# BSPD.net
KiCad netlist of a schematic drawn in Altium Designer
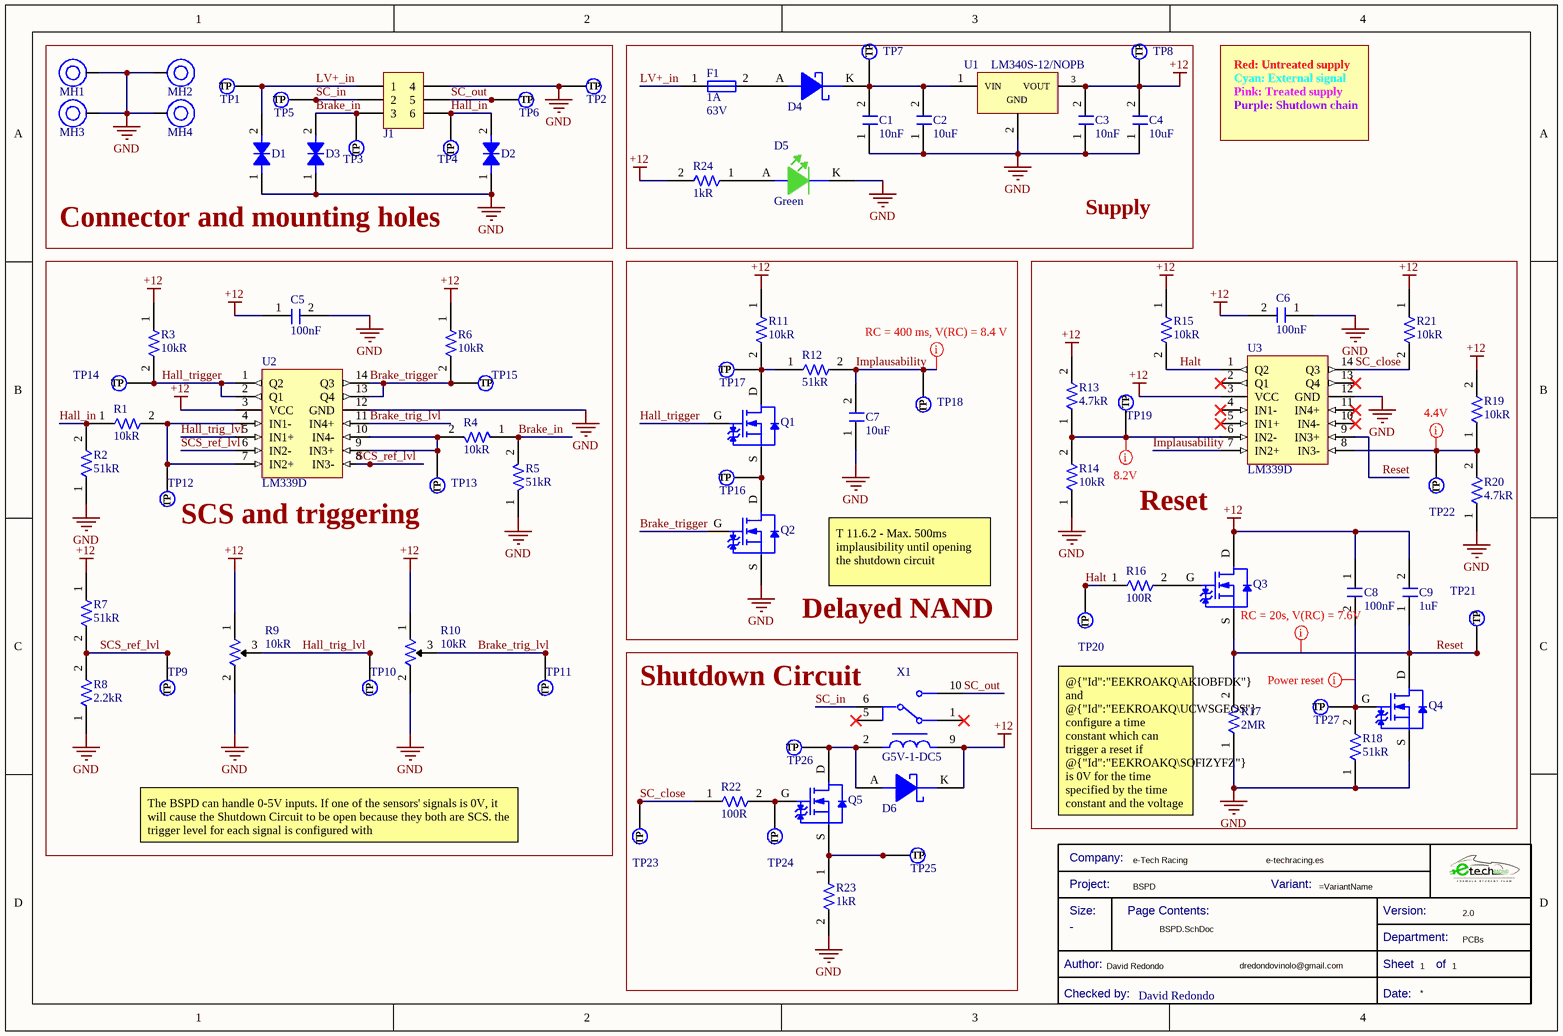
[diagram p0: BSPD.SchDoc]

(export (version "E")
  (design (tool "Eeschema 10.0.6"))
  (components
    (comp (ref "*")
      (value "Title Block_template")
      (description "Standard Title Block")
      (fields
        (field (name "SIZE") "-")
        (field (name ".CREATOR") "GP")
        (field (name ".PCBCHECK") "GP")
        (field (name ".SCHCHECK") "GP")
      )
      (libsource (lib "e-Tech_Racing") (part "Title Block_template"))
    )
    (comp (ref "C1")
      (value "885012008055")
      (footprint "C1206FNPC-RW")
      (description "Cap Cer 10000PF 50V C0G/NP0 1206")
      (fields
        (field (name "MANUFACTURER") "Wurth Electronics")
        (field (name "TOLERANCE") "5%")
        (field (name "CAPACITANCE") "10nF")
        (field (name ".CREATOR") "DO")
      )
      (libsource (lib "Passives") (part "C10n-50V-1206FNPC-C0G/NP0"))
    )
    (comp (ref "C2")
      (value "GRJ32ER71H106KE11L")
      (footprint "C10u-50V-1210FNPMLCC-X7R")
      (description "Multilayer Ceramic Capacitors MLCC - SMD/SMT 1210 10uF 50volts X7R +/-10% Soft Term")
      (fields
        (field (name "MANUFACTURER") "Murata")
        (field (name "TOLERANCE") "10%")
        (field (name "CAPACITANCE") "10uF")
        (field (name ".CREATOR") "DR")
      )
      (libsource (lib "Passives") (part "C10u-50V-1210FNPMLCC-X7R"))
    )
    (comp (ref "C3")
      (value "885012008055")
      (footprint "C1206FNPC-RW")
      (description "Cap Cer 10000PF 50V C0G/NP0 1206")
      (fields
        (field (name "MANUFACTURER") "Wurth Electronics")
        (field (name "TOLERANCE") "5%")
        (field (name "CAPACITANCE") "10nF")
        (field (name ".CREATOR") "DO")
      )
      (libsource (lib "Passives") (part "C10n-50V-1206FNPC-C0G/NP0"))
    )
    (comp (ref "C4")
      (value "GRJ32ER71H106KE11L")
      (footprint "C10u-50V-1210FNPMLCC-X7R")
      (description "Multilayer Ceramic Capacitors MLCC - SMD/SMT 1210 10uF 50volts X7R +/-10% Soft Term")
      (fields
        (field (name "MANUFACTURER") "Murata")
        (field (name "TOLERANCE") "10%")
        (field (name "CAPACITANCE") "10uF")
        (field (name ".CREATOR") "DR")
      )
      (libsource (lib "Passives") (part "C10u-50V-1210FNPMLCC-X7R"))
    )
    (comp (ref "C5")
      (value "885012208058")
      (footprint "C1206FNPC-RW")
      (description "Cap Cer 0.1UF 25V X7R 1206")
      (fields
        (field (name "MANUFACTURER") "Wurth Electronics")
        (field (name "TOLERANCE") "10%")
        (field (name "CAPACITANCE") "100nF")
        (field (name ".CREATOR") "DO")
      )
      (libsource (lib "Passives") (part "C100n-25V-1206FNPC-X7R"))
    )
    (comp (ref "C6")
      (value "885012208058")
      (footprint "C1206FNPC-RW")
      (description "Cap Cer 0.1UF 25V X7R 1206")
      (fields
        (field (name "MANUFACTURER") "Wurth Electronics")
        (field (name "TOLERANCE") "10%")
        (field (name "CAPACITANCE") "100nF")
        (field (name ".CREATOR") "DO")
      )
      (libsource (lib "Passives") (part "C100n-25V-1206FNPC-X7R"))
    )
    (comp (ref "C7")
      (value "885012208018")
      (footprint "C1206FNPC-RW")
      (description "Cap, 10ΜF, 10V, 10%, X7R, 1206")
      (fields
        (field (name "TOLERANCE") "10%")
        (field (name "CAPACITANCE") "10uF")
        (field (name ".CREATOR") "GP")
      )
      (libsource (lib "Passives") (part "C10u-10V-1206FNPC-X7R"))
    )
    (comp (ref "C8")
      (value "885012208058")
      (footprint "C1206FNPC-RW")
      (description "Cap Cer 0.1UF 25V X7R 1206")
      (fields
        (field (name "MANUFACTURER") "Wurth Electronics")
        (field (name "TOLERANCE") "10%")
        (field (name "CAPACITANCE") "100nF")
        (field (name ".CREATOR") "DO")
      )
      (libsource (lib "Passives") (part "C100n-25V-1206FNPC-X7R"))
    )
    (comp (ref "C9")
      (value "885012208036")
      (footprint "C1206FNPC-RW")
      (description "Cap Cer 1UF 16V X7R 1206")
      (fields
        (field (name "MANUFACTURER") "Wurth Electronics")
        (field (name "TOLERANCE") "10%")
        (field (name "CAPACITANCE") "1uF")
        (field (name ".CREATOR") "GP")
      )
      (libsource (lib "Passives") (part "C1u-16V-1206FNPC-X7R"))
    )
    (comp (ref "D1")
      (value "824551301")
      (footprint "DTVS-DO-214AB")
      (description "TVS diode [Würth Elektronik] 824551301 TVS diode")
      (fields (field (name "MANUFACTURER") "Wurth Electronics") (field (name ".CREATOR") "DO"))
      (libsource (lib "Filter components") (part "DTVS-40V-DO-214AB"))
    )
    (comp (ref "D2")
      (value "824501600")
      (footprint "DTVS-DO-214AC")
      (description "TVS diode [Würth Elektronik] 824501600 TVS diode")
      (fields (field (name "MANUFACTURER") "Wurth Electronics") (field (name ".CREATOR") "DO"))
      (libsource (lib "Filter components") (part "DTVS-6V-DO-214AC"))
    )
    (comp (ref "D3")
      (value "824501600")
      (footprint "DTVS-DO-214AC")
      (description "TVS diode [Würth Elektronik] 824501600 TVS diode")
      (fields (field (name "MANUFACTURER") "Wurth Electronics") (field (name ".CREATOR") "DO"))
      (libsource (lib "Filter components") (part "DTVS-6V-DO-214AC"))
    )
    (comp (ref "D4")
      (value "MBR0530")
      (footprint "DSC-SOD123")
      (description "VR=30V IF=500mA 30pF P=410mW")
      (fields (field (name ".CREATOR") "GP"))
      (libsource (lib "Filter components") (part "DSC-0.5/30-SOD123"))
    )
    (comp (ref "D5")
      (value "150080VS75000")
      (footprint "LED_0805_WE")
      (description "Led, Green, 570 Nm, 2 V, 30 Ma, 40 Mcd Rohs Compliant: Yes")
      (fields (field (name "COLOR") "Green") (field (name ".CREATOR") "DR"))
      (libsource (lib "Semiconductor") (part "LEDVS-0805-40"))
    )
    (comp (ref "D6")
      (value "MBR0530")
      (footprint "DSC-SOD123")
      (description "VR=30V IF=500mA 30pF P=410mW")
      (fields (field (name ".CREATOR") "GP"))
      (libsource (lib "Filter components") (part "DSC-0.5/30-SOD123"))
    )
    (comp (ref "F1")
      (value "0437001.WRA")
      (footprint "Fuse_1206")
      (description "Fuse Chip Fast Acting 1A 63V SMD Solder Pad 1206 Ceramic T/R Automotive")
      (fields
        (field (name "MANUFACTURER") "Littelfuse")
        (field (name "CURRENT RATING") "1A")
        (field (name "VOLTAGE RATING (DC)") "63V")
        (field (name ".CREATOR") "DO")
      )
      (libsource (lib "Filter components") (part "Fuse_1A_63V_1206"))
    )
    (comp (ref "J1")
      (value "J_NanoFit_2x3")
      (footprint "J_NanoFit_2x3")
      (libsource (lib "Electromechanical") (part "J_NanoFit_2x3"))
    )
    (comp (ref "MH1")
      (value "Mounting_Hole_M3")
      (footprint "Mounting_Hole_M3")
      (libsource (lib "Electromechanical") (part "Mounting_Hole_M3"))
    )
    (comp (ref "MH2")
      (value "Mounting_Hole_M3")
      (footprint "Mounting_Hole_M3")
      (libsource (lib "Electromechanical") (part "Mounting_Hole_M3"))
    )
    (comp (ref "MH3")
      (value "Mounting_Hole_M3")
      (footprint "Mounting_Hole_M3")
      (libsource (lib "Electromechanical") (part "Mounting_Hole_M3"))
    )
    (comp (ref "MH4")
      (value "Mounting_Hole_M3")
      (footprint "Mounting_Hole_M3")
      (libsource (lib "Electromechanical") (part "Mounting_Hole_M3"))
    )
    (comp (ref "Q1")
      (value "CPH3455-TL-H")
      (footprint "TRT-NCH-3/35-CPH")
      (description "CPH3455-TL-H N-channel MOSFET Transistor; 3 A; 35 V; 3-Pin CPH")
      (fields (field (name "MANUFACTURER") "ON Semiconductor") (field (name ".CREATOR") "GP"))
      (libsource (lib "Semiconductor") (part "TRT-NCH-3/35-CPH"))
    )
    (comp (ref "Q2")
      (value "CPH3455-TL-H")
      (footprint "TRT-NCH-3/35-CPH")
      (description "CPH3455-TL-H N-channel MOSFET Transistor; 3 A; 35 V; 3-Pin CPH")
      (fields (field (name "MANUFACTURER") "ON Semiconductor") (field (name ".CREATOR") "GP"))
      (libsource (lib "Semiconductor") (part "TRT-NCH-3/35-CPH"))
    )
    (comp (ref "Q3")
      (value "CPH3455-TL-H")
      (footprint "TRT-NCH-3/35-CPH")
      (description "CPH3455-TL-H N-channel MOSFET Transistor; 3 A; 35 V; 3-Pin CPH")
      (fields (field (name "MANUFACTURER") "ON Semiconductor") (field (name ".CREATOR") "GP"))
      (libsource (lib "Semiconductor") (part "TRT-NCH-3/35-CPH"))
    )
    (comp (ref "Q4")
      (value "CPH3455-TL-H")
      (footprint "TRT-NCH-3/35-CPH")
      (description "CPH3455-TL-H N-channel MOSFET Transistor; 3 A; 35 V; 3-Pin CPH")
      (fields (field (name "MANUFACTURER") "ON Semiconductor") (field (name ".CREATOR") "GP"))
      (libsource (lib "Semiconductor") (part "TRT-NCH-3/35-CPH"))
    )
    (comp (ref "Q5")
      (value "CPH3455-TL-H")
      (footprint "TRT-NCH-3/35-CPH")
      (description "CPH3455-TL-H N-channel MOSFET Transistor; 3 A; 35 V; 3-Pin CPH")
      (fields (field (name "MANUFACTURER") "ON Semiconductor") (field (name ".CREATOR") "GP"))
      (libsource (lib "Semiconductor") (part "TRT-NCH-3/35-CPH"))
    )
    (comp (ref "R1")
      (value "CRCW120610K0FKEA")
      (footprint "R1206FTK-W")
      (description "Res Thick Film 1206 10K Ohm 1% 0.25W(1/4W) +/-100ppm/ßC Pad SMD Automotive T/R")
      (fields (field (name "RESISTANCE") "10kR") (field (name ".CREATOR") "GP"))
      (libsource (lib "Passives") (part "R10k-1206FTK"))
    )
    (comp (ref "R2")
      (value "CRCW120610K0FKEA")
      (footprint "R1206FTK-W")
      (description "Res Thick Film 1206 51K Ohm 1% 1/4W ±100ppm/°C Molded SMD SMD Punched Carrier T/R")
      (fields
        (field (name "MANUFACTURER") "Panasonic")
        (field (name "MANUFACTURER PART NUMBER") "ERJ-S08F5102V")
        (field (name "RESISTANCE") "51kR")
        (field (name ".CREATOR") "DO")
      )
      (libsource (lib "Passives") (part "R51k-1206FTK"))
    )
    (comp (ref "R3")
      (value "CRCW120610K0FKEA")
      (footprint "R1206FTK-W")
      (description "Res Thick Film 1206 10K Ohm 1% 0.25W(1/4W) +/-100ppm/ßC Pad SMD Automotive T/R")
      (fields (field (name "RESISTANCE") "10kR") (field (name ".CREATOR") "GP"))
      (libsource (lib "Passives") (part "R10k-1206FTK"))
    )
    (comp (ref "R4")
      (value "CRCW120610K0FKEA")
      (footprint "R1206FTK-W")
      (description "Res Thick Film 1206 10K Ohm 1% 0.25W(1/4W) +/-100ppm/ßC Pad SMD Automotive T/R")
      (fields (field (name "RESISTANCE") "10kR") (field (name ".CREATOR") "GP"))
      (libsource (lib "Passives") (part "R10k-1206FTK"))
    )
    (comp (ref "R5")
      (value "CRCW120610K0FKEA")
      (footprint "R1206FTK-W")
      (description "Res Thick Film 1206 51K Ohm 1% 1/4W ±100ppm/°C Molded SMD SMD Punched Carrier T/R")
      (fields
        (field (name "MANUFACTURER") "Panasonic")
        (field (name "MANUFACTURER PART NUMBER") "ERJ-S08F5102V")
        (field (name "RESISTANCE") "51kR")
        (field (name ".CREATOR") "DO")
      )
      (libsource (lib "Passives") (part "R51k-1206FTK"))
    )
    (comp (ref "R6")
      (value "CRCW120610K0FKEA")
      (footprint "R1206FTK-W")
      (description "Res Thick Film 1206 10K Ohm 1% 0.25W(1/4W) +/-100ppm/ßC Pad SMD Automotive T/R")
      (fields (field (name "RESISTANCE") "10kR") (field (name ".CREATOR") "GP"))
      (libsource (lib "Passives") (part "R10k-1206FTK"))
    )
    (comp (ref "R7")
      (value "CRCW120610K0FKEA")
      (footprint "R1206FTK-W")
      (description "Res Thick Film 1206 51K Ohm 1% 1/4W ±100ppm/°C Molded SMD SMD Punched Carrier T/R")
      (fields
        (field (name "MANUFACTURER") "Panasonic")
        (field (name "MANUFACTURER PART NUMBER") "ERJ-S08F5102V")
        (field (name "RESISTANCE") "51kR")
        (field (name ".CREATOR") "DO")
      )
      (libsource (lib "Passives") (part "R51k-1206FTK"))
    )
    (comp (ref "R8")
      (value "CR1206-FX-2201ELF")
      (footprint "R1206FTK-W")
      (description "Res Thick Film 1206 2.2K Ohm 1% 1/4W ±100ppm/°C Molded SMD SMD Paper Tape on Plastic Reel")
      (fields
        (field (name "TOLERANCE") "1%")
        (field (name "RESISTANCE") "2.2kR")
        (field (name ".CREATOR") "AC")
      )
      (libsource (lib "Passives") (part "R2.2K-1206FTK"))
    )
    (comp (ref "R9")
      (value "3296W-1-103LF")
      (footprint "R10k-VTR")
      (description "Trimmer, Cermet, Rest 10 Kilohms, PCB, 25 Turns, Pwr-Rtg 0.5W, 3296 Series")
      (fields
        (field (name "MANUFACTURER") "Bourns")
        (field (name "TOLERANCE") "10%")
        (field (name "RESISTANCE") "10kR")
        (field (name ".CREATOR") "DO")
      )
      (libsource (lib "Passives") (part "R10k-VTR"))
    )
    (comp (ref "R10")
      (value "3296W-1-103LF")
      (footprint "R10k-VTR")
      (description "Trimmer, Cermet, Rest 10 Kilohms, PCB, 25 Turns, Pwr-Rtg 0.5W, 3296 Series")
      (fields
        (field (name "MANUFACTURER") "Bourns")
        (field (name "TOLERANCE") "10%")
        (field (name "RESISTANCE") "10kR")
        (field (name ".CREATOR") "DO")
      )
      (libsource (lib "Passives") (part "R10k-VTR"))
    )
    (comp (ref "R11")
      (value "CRCW120610K0FKEA")
      (footprint "R1206FTK-W")
      (description "Res Thick Film 1206 10K Ohm 1% 0.25W(1/4W) +/-100ppm/ßC Pad SMD Automotive T/R")
      (fields (field (name "RESISTANCE") "10kR") (field (name ".CREATOR") "GP"))
      (libsource (lib "Passives") (part "R10k-1206FTK"))
    )
    (comp (ref "R12")
      (value "CRCW120610K0FKEA")
      (footprint "R1206FTK-W")
      (description "Res Thick Film 1206 51K Ohm 1% 1/4W ±100ppm/°C Molded SMD SMD Punched Carrier T/R")
      (fields
        (field (name "MANUFACTURER") "Panasonic")
        (field (name "MANUFACTURER PART NUMBER") "ERJ-S08F5102V")
        (field (name "RESISTANCE") "51kR")
        (field (name ".CREATOR") "DO")
      )
      (libsource (lib "Passives") (part "R51k-1206FTK"))
    )
    (comp (ref "R13")
      (value "CRS1206-FX-4701ELF")
      (footprint "R1206FTK-W")
      (description "Res Thick Film 1206 4.7K Ohm 1% 1/2W ±100ppm/°C Molded SMD T/R")
      (fields
        (field (name "TOLERANCE") "1%")
        (field (name "RESISTANCE") "4.7kR")
        (field (name ".CREATOR") "AC")
      )
      (libsource (lib "Passives") (part "R4.7K-1206FTK"))
    )
    (comp (ref "R14")
      (value "CRCW120610K0FKEA")
      (footprint "R1206FTK-W")
      (description "Res Thick Film 1206 10K Ohm 1% 0.25W(1/4W) +/-100ppm/ßC Pad SMD Automotive T/R")
      (fields (field (name "RESISTANCE") "10kR") (field (name ".CREATOR") "GP"))
      (libsource (lib "Passives") (part "R10k-1206FTK"))
    )
    (comp (ref "R15")
      (value "CRCW120610K0FKEA")
      (footprint "R1206FTK-W")
      (description "Res Thick Film 1206 10K Ohm 1% 0.25W(1/4W) +/-100ppm/ßC Pad SMD Automotive T/R")
      (fields (field (name "RESISTANCE") "10kR") (field (name ".CREATOR") "GP"))
      (libsource (lib "Passives") (part "R10k-1206FTK"))
    )
    (comp (ref "R16")
      (value "CRG1206F100R")
      (footprint "R1206FTK-W")
      (description "Res Thick Film 1206 100 Ohm 1% 0.25W(1/4W) ±200ppm/C Pad SMD T/R")
      (fields
        (field (name "MANUFACTURER") "TE Connectivity")
        (field (name "TOLERANCE") "1%")
        (field (name "RESISTANCE") "100R")
        (field (name ".CREATOR") "AC")
      )
      (libsource (lib "Passives") (part "R100-1206FTK"))
    )
    (comp (ref "R17")
      (value "HVC1206-2M0FT3")
      (footprint "R1206FTK-W")
      (description "Res Thick Film 1206 2M Ohm 1% 0.3W ±100ppm/C Pad SMD T/R")
      (fields
        (field (name "MANUFACTURER") "TT Welwyn")
        (field (name "TOLERANCE") "1%")
        (field (name "RESISTENCE") "2MR")
        (field (name ".CREATOR") "DO")
      )
      (libsource (lib "Passives") (part "R2M-1206FTK"))
    )
    (comp (ref "R18")
      (value "CRCW120610K0FKEA")
      (footprint "R1206FTK-W")
      (description "Res Thick Film 1206 51K Ohm 1% 1/4W ±100ppm/°C Molded SMD SMD Punched Carrier T/R")
      (fields
        (field (name "MANUFACTURER") "Panasonic")
        (field (name "MANUFACTURER PART NUMBER") "ERJ-S08F5102V")
        (field (name "RESISTANCE") "51kR")
        (field (name ".CREATOR") "DO")
      )
      (libsource (lib "Passives") (part "R51k-1206FTK"))
    )
    (comp (ref "R19")
      (value "CRCW120610K0FKEA")
      (footprint "R1206FTK-W")
      (description "Res Thick Film 1206 10K Ohm 1% 0.25W(1/4W) +/-100ppm/ßC Pad SMD Automotive T/R")
      (fields (field (name "RESISTANCE") "10kR") (field (name ".CREATOR") "GP"))
      (libsource (lib "Passives") (part "R10k-1206FTK"))
    )
    (comp (ref "R20")
      (value "CRS1206-FX-4701ELF")
      (footprint "R1206FTK-W")
      (description "Res Thick Film 1206 4.7K Ohm 1% 1/2W ±100ppm/°C Molded SMD T/R")
      (fields
        (field (name "TOLERANCE") "1%")
        (field (name "RESISTANCE") "4.7kR")
        (field (name ".CREATOR") "AC")
      )
      (libsource (lib "Passives") (part "R4.7K-1206FTK"))
    )
    (comp (ref "R21")
      (value "CRCW120610K0FKEA")
      (footprint "R1206FTK-W")
      (description "Res Thick Film 1206 10K Ohm 1% 0.25W(1/4W) +/-100ppm/ßC Pad SMD Automotive T/R")
      (fields (field (name "RESISTANCE") "10kR") (field (name ".CREATOR") "GP"))
      (libsource (lib "Passives") (part "R10k-1206FTK"))
    )
    (comp (ref "R22")
      (value "CRG1206F100R")
      (footprint "R1206FTK-W")
      (description "Res Thick Film 1206 100 Ohm 1% 0.25W(1/4W) ±200ppm/C Pad SMD T/R")
      (fields
        (field (name "MANUFACTURER") "TE Connectivity")
        (field (name "TOLERANCE") "1%")
        (field (name "RESISTANCE") "100R")
        (field (name ".CREATOR") "AC")
      )
      (libsource (lib "Passives") (part "R100-1206FTK"))
    )
    (comp (ref "R23")
      (value "ERJT08J102V")
      (footprint "R1206FTK-W")
      (description "Res Thick Film 1206 1K Ohm 5% 0.33W(1/3W) ±200ppm/C Pad SMD Automotive T/R")
      (fields
        (field (name "MANUFACTURER") "Panasonic")
        (field (name "TOLERANCE") "5%")
        (field (name "RESISTANCE") "1kR")
        (field (name ".CREATOR") "GP")
      )
      (libsource (lib "Passives") (part "R1k-1206FTK"))
    )
    (comp (ref "R24")
      (value "CR0805-JW-102ELF")
      (footprint "R0805FTK")
      (description "Res Thick Film 0805 1K Ohm 5% 1/8W ±200ppm/°C Molded SMD SMD Paper Tape on Plastic Reel")
      (fields
        (field (name "TOLERANCE") "5%")
        (field (name "RESISTANCE") "1kR")
        (field (name ".CREATOR") "GP")
      )
      (libsource (lib "Passives") (part "R1k-0805FTK"))
    )
    (comp (ref "TP1")
      (value "TestPoint")
      (footprint "TestPoint")
      (description "Test Point 1x1 mm")
      (fields (field (name ".CREATOR") "GP") (field (name ".PCBCHECK") "GP") (field (name ".SCHCHECK") "GP"))
      (libsource (lib "e-Tech_Racing") (part "TestPoint"))
    )
    (comp (ref "TP2")
      (value "TestPoint")
      (footprint "TestPoint")
      (description "Test Point 1x1 mm")
      (fields (field (name ".CREATOR") "GP") (field (name ".PCBCHECK") "GP") (field (name ".SCHCHECK") "GP"))
      (libsource (lib "e-Tech_Racing") (part "TestPoint"))
    )
    (comp (ref "TP3")
      (value "TestPoint")
      (footprint "TestPoint")
      (description "Test Point 1x1 mm")
      (fields (field (name ".CREATOR") "GP") (field (name ".PCBCHECK") "GP") (field (name ".SCHCHECK") "GP"))
      (libsource (lib "e-Tech_Racing") (part "TestPoint"))
    )
    (comp (ref "TP4")
      (value "TestPoint")
      (footprint "TestPoint")
      (description "Test Point 1x1 mm")
      (fields (field (name ".CREATOR") "GP") (field (name ".PCBCHECK") "GP") (field (name ".SCHCHECK") "GP"))
      (libsource (lib "e-Tech_Racing") (part "TestPoint"))
    )
    (comp (ref "TP5")
      (value "TestPoint")
      (footprint "TestPoint")
      (description "Test Point 1x1 mm")
      (fields (field (name ".CREATOR") "GP") (field (name ".PCBCHECK") "GP") (field (name ".SCHCHECK") "GP"))
      (libsource (lib "e-Tech_Racing") (part "TestPoint"))
    )
    (comp (ref "TP6")
      (value "TestPoint")
      (footprint "TestPoint")
      (description "Test Point 1x1 mm")
      (fields (field (name ".CREATOR") "GP") (field (name ".PCBCHECK") "GP") (field (name ".SCHCHECK") "GP"))
      (libsource (lib "e-Tech_Racing") (part "TestPoint"))
    )
    (comp (ref "TP7")
      (value "TestPoint")
      (footprint "TestPoint")
      (description "Test Point 1x1 mm")
      (fields (field (name ".CREATOR") "GP") (field (name ".PCBCHECK") "GP") (field (name ".SCHCHECK") "GP"))
      (libsource (lib "e-Tech_Racing") (part "TestPoint"))
    )
    (comp (ref "TP8")
      (value "TestPoint")
      (footprint "TestPoint")
      (description "Test Point 1x1 mm")
      (fields (field (name ".CREATOR") "GP") (field (name ".PCBCHECK") "GP") (field (name ".SCHCHECK") "GP"))
      (libsource (lib "e-Tech_Racing") (part "TestPoint"))
    )
    (comp (ref "TP9")
      (value "TestPoint")
      (footprint "TestPoint")
      (description "Test Point 1x1 mm")
      (fields (field (name ".CREATOR") "GP") (field (name ".PCBCHECK") "GP") (field (name ".SCHCHECK") "GP"))
      (libsource (lib "e-Tech_Racing") (part "TestPoint"))
    )
    (comp (ref "TP10")
      (value "TestPoint")
      (footprint "TestPoint")
      (description "Test Point 1x1 mm")
      (fields (field (name ".CREATOR") "GP") (field (name ".PCBCHECK") "GP") (field (name ".SCHCHECK") "GP"))
      (libsource (lib "e-Tech_Racing") (part "TestPoint"))
    )
    (comp (ref "TP11")
      (value "TestPoint")
      (footprint "TestPoint")
      (description "Test Point 1x1 mm")
      (fields (field (name ".CREATOR") "GP") (field (name ".PCBCHECK") "GP") (field (name ".SCHCHECK") "GP"))
      (libsource (lib "e-Tech_Racing") (part "TestPoint"))
    )
    (comp (ref "TP12")
      (value "TestPoint")
      (footprint "TestPoint")
      (description "Test Point 1x1 mm")
      (fields (field (name ".CREATOR") "GP") (field (name ".PCBCHECK") "GP") (field (name ".SCHCHECK") "GP"))
      (libsource (lib "e-Tech_Racing") (part "TestPoint"))
    )
    (comp (ref "TP13")
      (value "TestPoint")
      (footprint "TestPoint")
      (description "Test Point 1x1 mm")
      (fields (field (name ".CREATOR") "GP") (field (name ".PCBCHECK") "GP") (field (name ".SCHCHECK") "GP"))
      (libsource (lib "e-Tech_Racing") (part "TestPoint"))
    )
    (comp (ref "TP14")
      (value "TestPoint")
      (footprint "TestPoint")
      (description "Test Point 1x1 mm")
      (fields (field (name ".CREATOR") "GP") (field (name ".PCBCHECK") "GP") (field (name ".SCHCHECK") "GP"))
      (libsource (lib "e-Tech_Racing") (part "TestPoint"))
    )
    (comp (ref "TP15")
      (value "TestPoint")
      (footprint "TestPoint")
      (description "Test Point 1x1 mm")
      (fields (field (name ".CREATOR") "GP") (field (name ".PCBCHECK") "GP") (field (name ".SCHCHECK") "GP"))
      (libsource (lib "e-Tech_Racing") (part "TestPoint"))
    )
    (comp (ref "TP16")
      (value "TestPoint")
      (footprint "TestPoint")
      (description "Test Point 1x1 mm")
      (fields (field (name ".CREATOR") "GP") (field (name ".PCBCHECK") "GP") (field (name ".SCHCHECK") "GP"))
      (libsource (lib "e-Tech_Racing") (part "TestPoint"))
    )
    (comp (ref "TP17")
      (value "TestPoint")
      (footprint "TestPoint")
      (description "Test Point 1x1 mm")
      (fields (field (name ".CREATOR") "GP") (field (name ".PCBCHECK") "GP") (field (name ".SCHCHECK") "GP"))
      (libsource (lib "e-Tech_Racing") (part "TestPoint"))
    )
    (comp (ref "TP18")
      (value "TestPoint")
      (footprint "TestPoint")
      (description "Test Point 1x1 mm")
      (fields (field (name ".CREATOR") "GP") (field (name ".PCBCHECK") "GP") (field (name ".SCHCHECK") "GP"))
      (libsource (lib "e-Tech_Racing") (part "TestPoint"))
    )
    (comp (ref "TP19")
      (value "TestPoint")
      (footprint "TestPoint")
      (description "Test Point 1x1 mm")
      (fields (field (name ".CREATOR") "GP") (field (name ".PCBCHECK") "GP") (field (name ".SCHCHECK") "GP"))
      (libsource (lib "e-Tech_Racing") (part "TestPoint"))
    )
    (comp (ref "TP20")
      (value "TestPoint")
      (footprint "TestPoint")
      (description "Test Point 1x1 mm")
      (fields (field (name ".CREATOR") "GP") (field (name ".PCBCHECK") "GP") (field (name ".SCHCHECK") "GP"))
      (libsource (lib "e-Tech_Racing") (part "TestPoint"))
    )
    (comp (ref "TP21")
      (value "TestPoint")
      (footprint "TestPoint")
      (description "Test Point 1x1 mm")
      (fields (field (name ".CREATOR") "GP") (field (name ".PCBCHECK") "GP") (field (name ".SCHCHECK") "GP"))
      (libsource (lib "e-Tech_Racing") (part "TestPoint"))
    )
    (comp (ref "TP22")
      (value "TestPoint")
      (footprint "TestPoint")
      (description "Test Point 1x1 mm")
      (fields (field (name ".CREATOR") "GP") (field (name ".PCBCHECK") "GP") (field (name ".SCHCHECK") "GP"))
      (libsource (lib "e-Tech_Racing") (part "TestPoint"))
    )
    (comp (ref "TP23")
      (value "TestPoint")
      (footprint "TestPoint")
      (description "Test Point 1x1 mm")
      (fields (field (name ".CREATOR") "GP") (field (name ".PCBCHECK") "GP") (field (name ".SCHCHECK") "GP"))
      (libsource (lib "e-Tech_Racing") (part "TestPoint"))
    )
    (comp (ref "TP24")
      (value "TestPoint")
      (footprint "TestPoint")
      (description "Test Point 1x1 mm")
      (fields (field (name ".CREATOR") "GP") (field (name ".PCBCHECK") "GP") (field (name ".SCHCHECK") "GP"))
      (libsource (lib "e-Tech_Racing") (part "TestPoint"))
    )
    (comp (ref "TP25")
      (value "TestPoint")
      (footprint "TestPoint")
      (description "Test Point 1x1 mm")
      (fields (field (name ".CREATOR") "GP") (field (name ".PCBCHECK") "GP") (field (name ".SCHCHECK") "GP"))
      (libsource (lib "e-Tech_Racing") (part "TestPoint"))
    )
    (comp (ref "TP26")
      (value "TestPoint")
      (footprint "TestPoint")
      (description "Test Point 1x1 mm")
      (fields (field (name ".CREATOR") "GP") (field (name ".PCBCHECK") "GP") (field (name ".SCHCHECK") "GP"))
      (libsource (lib "e-Tech_Racing") (part "TestPoint"))
    )
    (comp (ref "TP27")
      (value "TestPoint")
      (footprint "TestPoint")
      (description "Test Point 1x1 mm")
      (fields (field (name ".CREATOR") "GP") (field (name ".PCBCHECK") "GP") (field (name ".SCHCHECK") "GP"))
      (libsource (lib "e-Tech_Racing") (part "TestPoint"))
    )
    (comp (ref "U1")
      (value "LM340S-12/NOPB")
      (footprint "LDO_35V-1/12V-TO220")
      (description "1.5-A, 35-V, linear voltage regulator 3-TO-220 -40 to 125")
      (fields
        (field (name "MANUFACTURER") "Texas Instruments")
        (field (name "VOLTAGE") "12V")
        (field (name "MANUFACTURER PART NUMBER") "LM340S-12/NOPB")
        (field (name ".CREATOR") "AC")
      )
      (libsource (lib "Semiconductor") (part "LDO_35V-1/12V-TO220"))
    )
    (comp (ref "U2")
      (value "LM339D")
      (footprint "Array_4_Amp_LM339D")
      (description "Comparator Quad ±18V/36V 14-Pin SOIC Tube")
      (fields
        (field (name "MANUFACTURER") "Texas Instruments")
        (field (name "MANUFACTURER PART NUMBER") "LM339D")
        (field (name ".CREATOR") "DO")
      )
      (libsource (lib "Integrated circuits") (part "Array_4_Comp_LM339D"))
    )
    (comp (ref "U3")
      (value "LM339D")
      (footprint "Array_4_Amp_LM339D")
      (description "Comparator Quad ±18V/36V 14-Pin SOIC Tube")
      (fields
        (field (name "MANUFACTURER") "Texas Instruments")
        (field (name "MANUFACTURER PART NUMBER") "LM339D")
        (field (name ".CREATOR") "DO")
      )
      (libsource (lib "Integrated circuits") (part "Array_4_Comp_LM339D"))
    )
    (comp (ref "X1")
      (value "G5V-1-DC5")
      (footprint "Relay_G5V-1-DC5")
      (description "Electromechanical Relay SPDT 1A 5VDC 167Ohm Through Hole")
      (fields
        (field (name "MANUFACTURER") "Omron")
        (field (name "SUPPLIER PART NUMBER 1") "G5V-1-DC5")
        (field (name ".CREATOR") "DO")
      )
      (libsource (lib "Electromechanical") (part "Relay_G5V-1-DC5"))
    )
  )
  (nets
    (net (code "1") (name "+12") (class "Default")
      (node (ref "C3") (pin "2") (pinfunction "2_2") (pintype "passive"))
      (node (ref "C4") (pin "2") (pinfunction "2_2") (pintype "passive"))
      (node (ref "C5") (pin "1") (pinfunction "1_1") (pintype "passive"))
      (node (ref "C6") (pin "2") (pinfunction "2_2") (pintype "passive"))
      (node (ref "C8") (pin "1") (pinfunction "1_1") (pintype "passive"))
      (node (ref "C9") (pin "2") (pinfunction "2_2") (pintype "passive"))
      (node (ref "D6") (pin "K") (pinfunction "K_K") (pintype "passive"))
      (node (ref "Q3") (pin "D") (pinfunction "D_D") (pintype "passive"))
      (node (ref "R10") (pin "1") (pinfunction "2_1") (pintype "passive"))
      (node (ref "R11") (pin "1") (pinfunction "1_1") (pintype "passive"))
      (node (ref "R13") (pin "2") (pinfunction "2_2") (pintype "passive"))
      (node (ref "R15") (pin "1") (pinfunction "1_1") (pintype "passive"))
      (node (ref "R19") (pin "2") (pinfunction "2_2") (pintype "passive"))
      (node (ref "R21") (pin "1") (pinfunction "1_1") (pintype "passive"))
      (node (ref "R24") (pin "2") (pinfunction "2_2") (pintype "passive"))
      (node (ref "R3") (pin "1") (pinfunction "1_1") (pintype "passive"))
      (node (ref "R6") (pin "1") (pinfunction "1_1") (pintype "passive"))
      (node (ref "R7") (pin "1") (pinfunction "1_1") (pintype "passive"))
      (node (ref "R9") (pin "1") (pinfunction "2_1") (pintype "passive"))
      (node (ref "TP8") (pin "1") (pinfunction "TP_1") (pintype "passive"))
      (node (ref "U1") (pin "3") (pinfunction "VOUT_3") (pintype "passive"))
      (node (ref "U2") (pin "3") (pinfunction "VCC_3") (pintype "power_in"))
      (node (ref "U3") (pin "3") (pinfunction "VCC_3") (pintype "power_in"))
      (node (ref "X1") (pin "9") (pinfunction "9_9") (pintype "passive"))
    )
    (net (code "2") (name "/Brake_in") (class "Default")
      (node (ref "D3") (pin "2") (pinfunction "2_2") (pintype "passive"))
      (node (ref "J1") (pin "3") (pinfunction "3_3") (pintype "passive"))
      (node (ref "R4") (pin "1") (pinfunction "1_1") (pintype "passive"))
      (node (ref "R5") (pin "2") (pinfunction "2_2") (pintype "passive"))
      (node (ref "TP3") (pin "1") (pinfunction "TP_1") (pintype "passive"))
    )
    (net (code "3") (name "/Brake_trig_lvl") (class "Default")
      (node (ref "R10") (pin "3") (pinfunction "3_3") (pintype "passive"))
      (node (ref "TP11") (pin "1") (pinfunction "TP_1") (pintype "passive"))
      (node (ref "U2") (pin "11") (pinfunction "IN4+_11") (pintype "input"))
    )
    (net (code "4") (name "/Brake_trigger") (class "Default")
      (node (ref "Q2") (pin "G") (pinfunction "G_G") (pintype "passive"))
      (node (ref "R6") (pin "2") (pinfunction "2_2") (pintype "passive"))
      (node (ref "TP15") (pin "1") (pinfunction "TP_1") (pintype "passive"))
      (node (ref "U2") (pin "13") (pinfunction "Q4_13") (pintype "output"))
      (node (ref "U2") (pin "14") (pinfunction "Q3_14") (pintype "output"))
    )
    (net (code "5") (name "/Hall_in") (class "Default")
      (node (ref "D2") (pin "2") (pinfunction "2_2") (pintype "passive"))
      (node (ref "J1") (pin "6") (pinfunction "6_6") (pintype "passive"))
      (node (ref "R1") (pin "1") (pinfunction "1_1") (pintype "passive"))
      (node (ref "R2") (pin "2") (pinfunction "2_2") (pintype "passive"))
      (node (ref "TP4") (pin "1") (pinfunction "TP_1") (pintype "passive"))
    )
    (net (code "6") (name "/Hall_trig_lvl") (class "Default")
      (node (ref "R9") (pin "3") (pinfunction "3_3") (pintype "passive"))
      (node (ref "TP10") (pin "1") (pinfunction "TP_1") (pintype "passive"))
      (node (ref "U2") (pin "5") (pinfunction "IN1+_5") (pintype "input"))
    )
    (net (code "7") (name "/Hall_trigger") (class "Default")
      (node (ref "Q1") (pin "G") (pinfunction "G_G") (pintype "passive"))
      (node (ref "R3") (pin "2") (pinfunction "2_2") (pintype "passive"))
      (node (ref "TP14") (pin "1") (pinfunction "TP_1") (pintype "passive"))
      (node (ref "U2") (pin "1") (pinfunction "Q2_1") (pintype "output"))
      (node (ref "U2") (pin "2") (pinfunction "Q1_2") (pintype "output"))
    )
    (net (code "8") (name "/Halt") (class "Default")
      (node (ref "R15") (pin "2") (pinfunction "2_2") (pintype "passive"))
      (node (ref "R16") (pin "1") (pinfunction "1_1") (pintype "passive"))
      (node (ref "TP20") (pin "1") (pinfunction "TP_1") (pintype "passive"))
      (node (ref "U3") (pin "1") (pinfunction "Q2_1") (pintype "output"))
    )
    (net (code "9") (name "/Implausability") (class "Default")
      (node (ref "C7") (pin "2") (pinfunction "2_2") (pintype "passive"))
      (node (ref "R12") (pin "2") (pinfunction "2_2") (pintype "passive"))
      (node (ref "TP18") (pin "1") (pinfunction "TP_1") (pintype "passive"))
      (node (ref "U3") (pin "7") (pinfunction "IN2+_7") (pintype "input"))
    )
    (net (code "10") (name "/LV+_in") (class "Default")
      (node (ref "D1") (pin "2") (pinfunction "2_2") (pintype "passive"))
      (node (ref "F1") (pin "1") (pinfunction "1_1") (pintype "passive"))
      (node (ref "J1") (pin "1") (pinfunction "1_1") (pintype "passive"))
      (node (ref "TP1") (pin "1") (pinfunction "TP_1") (pintype "passive"))
    )
    (net (code "11") (name "/Reset") (class "Default")
      (node (ref "C9") (pin "1") (pinfunction "1_1") (pintype "passive"))
      (node (ref "Q3") (pin "S") (pinfunction "S_S") (pintype "passive"))
      (node (ref "Q4") (pin "D") (pinfunction "D_D") (pintype "passive"))
      (node (ref "R17") (pin "2") (pinfunction "2_2") (pintype "passive"))
      (node (ref "TP21") (pin "1") (pinfunction "TP_1") (pintype "passive"))
      (node (ref "U3") (pin "9") (pinfunction "IN3+_9") (pintype "input"))
    )
    (net (code "12") (name "/SCS_ref_lvl") (class "Default")
      (node (ref "R7") (pin "2") (pinfunction "2_2") (pintype "passive"))
      (node (ref "R8") (pin "2") (pinfunction "2_2") (pintype "passive"))
      (node (ref "TP9") (pin "1") (pinfunction "TP_1") (pintype "passive"))
      (node (ref "U2") (pin "6") (pinfunction "IN2-_6") (pintype "input"))
      (node (ref "U2") (pin "8") (pinfunction "IN3-_8") (pintype "input"))
    )
    (net (code "13") (name "/SC_close") (class "Default")
      (node (ref "R21") (pin "2") (pinfunction "2_2") (pintype "passive"))
      (node (ref "R22") (pin "1") (pinfunction "1_1") (pintype "passive"))
      (node (ref "TP23") (pin "1") (pinfunction "TP_1") (pintype "passive"))
      (node (ref "U3") (pin "14") (pinfunction "Q3_14") (pintype "output"))
    )
    (net (code "14") (name "/SC_in") (class "Default")
      (node (ref "J1") (pin "2") (pinfunction "2_2") (pintype "passive"))
      (node (ref "TP5") (pin "1") (pinfunction "TP_1") (pintype "passive"))
      (node (ref "X1") (pin "6") (pinfunction "6_6") (pintype "passive"))
    )
    (net (code "15") (name "/SC_out") (class "Default")
      (node (ref "J1") (pin "5") (pinfunction "5_5") (pintype "passive"))
      (node (ref "TP6") (pin "1") (pinfunction "TP_1") (pintype "passive"))
      (node (ref "X1") (pin "10") (pinfunction "10_10") (pintype "passive"))
    )
    (net (code "16") (name "GND") (class "Default")
      (node (ref "C1") (pin "1") (pinfunction "1_1") (pintype "passive"))
      (node (ref "C2") (pin "1") (pinfunction "1_1") (pintype "passive"))
      (node (ref "C3") (pin "1") (pinfunction "1_1") (pintype "passive"))
      (node (ref "C4") (pin "1") (pinfunction "1_1") (pintype "passive"))
      (node (ref "C5") (pin "2") (pinfunction "2_2") (pintype "passive"))
      (node (ref "C6") (pin "1") (pinfunction "1_1") (pintype "passive"))
      (node (ref "C7") (pin "1") (pinfunction "1_1") (pintype "passive"))
      (node (ref "D1") (pin "1") (pinfunction "1_1") (pintype "passive"))
      (node (ref "D2") (pin "1") (pinfunction "1_1") (pintype "passive"))
      (node (ref "D3") (pin "1") (pinfunction "1_1") (pintype "passive"))
      (node (ref "D5") (pin "K") (pinfunction "K_K") (pintype "passive"))
      (node (ref "J1") (pin "4") (pinfunction "4_4") (pintype "passive"))
      (node (ref "MH1") (pin "1") (pinfunction "1_1") (pintype "passive"))
      (node (ref "MH2") (pin "1") (pinfunction "1_1") (pintype "passive"))
      (node (ref "MH3") (pin "1") (pinfunction "1_1") (pintype "passive"))
      (node (ref "MH4") (pin "1") (pinfunction "1_1") (pintype "passive"))
      (node (ref "Q2") (pin "S") (pinfunction "S_S") (pintype "passive"))
      (node (ref "Q4") (pin "S") (pinfunction "S_S") (pintype "passive"))
      (node (ref "R10") (pin "2") (pinfunction "2_2") (pintype "passive"))
      (node (ref "R14") (pin "1") (pinfunction "1_1") (pintype "passive"))
      (node (ref "R17") (pin "1") (pinfunction "1_1") (pintype "passive"))
      (node (ref "R18") (pin "1") (pinfunction "1_1") (pintype "passive"))
      (node (ref "R2") (pin "1") (pinfunction "1_1") (pintype "passive"))
      (node (ref "R20") (pin "1") (pinfunction "1_1") (pintype "passive"))
      (node (ref "R23") (pin "2") (pinfunction "2_2") (pintype "passive"))
      (node (ref "R5") (pin "1") (pinfunction "1_1") (pintype "passive"))
      (node (ref "R8") (pin "1") (pinfunction "1_1") (pintype "passive"))
      (node (ref "R9") (pin "2") (pinfunction "2_2") (pintype "passive"))
      (node (ref "TP2") (pin "1") (pinfunction "TP_1") (pintype "passive"))
      (node (ref "U1") (pin "2") (pinfunction "GND_2") (pintype "passive"))
      (node (ref "U2") (pin "12") (pinfunction "GND_12") (pintype "power_in"))
      (node (ref "U3") (pin "12") (pinfunction "GND_12") (pintype "power_in"))
    )
    (net (code "17") (name "Net-(D4-PadA)") (class "Default")
      (node (ref "D4") (pin "A") (pinfunction "A_A") (pintype "passive"))
      (node (ref "F1") (pin "2") (pinfunction "2_2") (pintype "passive"))
    )
    (net (code "18") (name "Net-(D5-PadA)") (class "Default")
      (node (ref "D5") (pin "A") (pinfunction "A_A") (pintype "passive"))
      (node (ref "R24") (pin "1") (pinfunction "1_1") (pintype "passive"))
    )
    (net (code "19") (name "Net-(Q3-PadG)") (class "Default")
      (node (ref "Q3") (pin "G") (pinfunction "G_G") (pintype "passive"))
      (node (ref "R16") (pin "2") (pinfunction "2_2") (pintype "passive"))
    )
    (net (code "20") (name "Net-(TP7-TP)") (class "Default")
      (node (ref "C1") (pin "2") (pinfunction "2_2") (pintype "passive"))
      (node (ref "C2") (pin "2") (pinfunction "2_2") (pintype "passive"))
      (node (ref "D4") (pin "K") (pinfunction "K_K") (pintype "passive"))
      (node (ref "TP7") (pin "1") (pinfunction "TP_1") (pintype "passive"))
      (node (ref "U1") (pin "1") (pinfunction "VIN_1") (pintype "passive"))
    )
    (net (code "21") (name "Net-(TP12-TP)") (class "Default")
      (node (ref "R1") (pin "2") (pinfunction "2_2") (pintype "passive"))
      (node (ref "TP12") (pin "1") (pinfunction "TP_1") (pintype "passive"))
      (node (ref "U2") (pin "4") (pinfunction "IN1-_4") (pintype "input"))
      (node (ref "U2") (pin "7") (pinfunction "IN2+_7") (pintype "input"))
    )
    (net (code "22") (name "Net-(TP13-TP)") (class "Default")
      (node (ref "R4") (pin "2") (pinfunction "2_2") (pintype "passive"))
      (node (ref "TP13") (pin "1") (pinfunction "TP_1") (pintype "passive"))
      (node (ref "U2") (pin "10") (pinfunction "IN4-_10") (pintype "input"))
      (node (ref "U2") (pin "9") (pinfunction "IN3+_9") (pintype "input"))
    )
    (net (code "23") (name "Net-(TP16-TP)") (class "Default")
      (node (ref "Q1") (pin "S") (pinfunction "S_S") (pintype "passive"))
      (node (ref "Q2") (pin "D") (pinfunction "D_D") (pintype "passive"))
      (node (ref "TP16") (pin "1") (pinfunction "TP_1") (pintype "passive"))
    )
    (net (code "24") (name "Net-(TP17-TP)") (class "Default")
      (node (ref "Q1") (pin "D") (pinfunction "D_D") (pintype "passive"))
      (node (ref "R11") (pin "2") (pinfunction "2_2") (pintype "passive"))
      (node (ref "R12") (pin "1") (pinfunction "1_1") (pintype "passive"))
      (node (ref "TP17") (pin "1") (pinfunction "TP_1") (pintype "passive"))
    )
    (net (code "25") (name "Net-(TP19-TP)") (class "Default")
      (node (ref "R13") (pin "1") (pinfunction "1_1") (pintype "passive"))
      (node (ref "R14") (pin "2") (pinfunction "2_2") (pintype "passive"))
      (node (ref "TP19") (pin "1") (pinfunction "TP_1") (pintype "passive"))
      (node (ref "U3") (pin "6") (pinfunction "IN2-_6") (pintype "input"))
    )
    (net (code "26") (name "Net-(TP22-TP)") (class "Default")
      (node (ref "R19") (pin "1") (pinfunction "1_1") (pintype "passive"))
      (node (ref "R20") (pin "2") (pinfunction "2_2") (pintype "passive"))
      (node (ref "TP22") (pin "1") (pinfunction "TP_1") (pintype "passive"))
      (node (ref "U3") (pin "8") (pinfunction "IN3-_8") (pintype "input"))
    )
    (net (code "27") (name "Net-(TP24-TP)") (class "Default")
      (node (ref "Q5") (pin "G") (pinfunction "G_G") (pintype "passive"))
      (node (ref "R22") (pin "2") (pinfunction "2_2") (pintype "passive"))
      (node (ref "TP24") (pin "1") (pinfunction "TP_1") (pintype "passive"))
    )
    (net (code "28") (name "Net-(TP25-TP)") (class "Default")
      (node (ref "Q5") (pin "S") (pinfunction "S_S") (pintype "passive"))
      (node (ref "R23") (pin "1") (pinfunction "1_1") (pintype "passive"))
      (node (ref "TP25") (pin "1") (pinfunction "TP_1") (pintype "passive"))
    )
    (net (code "29") (name "Net-(TP26-TP)") (class "Default")
      (node (ref "D6") (pin "A") (pinfunction "A_A") (pintype "passive"))
      (node (ref "Q5") (pin "D") (pinfunction "D_D") (pintype "passive"))
      (node (ref "TP26") (pin "1") (pinfunction "TP_1") (pintype "passive"))
      (node (ref "X1") (pin "2") (pinfunction "2_2") (pintype "passive"))
    )
    (net (code "30") (name "Net-(TP27-TP)") (class "Default")
      (node (ref "C8") (pin "2") (pinfunction "2_2") (pintype "passive"))
      (node (ref "Q4") (pin "G") (pinfunction "G_G") (pintype "passive"))
      (node (ref "R18") (pin "2") (pinfunction "2_2") (pintype "passive"))
      (node (ref "TP27") (pin "1") (pinfunction "TP_1") (pintype "passive"))
    )
    (net (code "31") (name "unconnected-(U3-IN1+-Pad5)") (class "Default")
      (node (ref "U3") (pin "5") (pinfunction "IN1+_5") (pintype "input+no_connect"))
    )
    (net (code "32") (name "unconnected-(U3-IN1--Pad4)") (class "Default")
      (node (ref "U3") (pin "4") (pinfunction "IN1-_4") (pintype "input+no_connect"))
    )
    (net (code "33") (name "unconnected-(U3-IN4+-Pad11)") (class "Default")
      (node (ref "U3") (pin "11") (pinfunction "IN4+_11") (pintype "input+no_connect"))
    )
    (net (code "34") (name "unconnected-(U3-IN4--Pad10)") (class "Default")
      (node (ref "U3") (pin "10") (pinfunction "IN4-_10") (pintype "input+no_connect"))
    )
    (net (code "35") (name "unconnected-(U3-Q1-Pad2)") (class "Default")
      (node (ref "U3") (pin "2") (pinfunction "Q1_2") (pintype "output+no_connect"))
    )
    (net (code "36") (name "unconnected-(U3-Q4-Pad13)") (class "Default")
      (node (ref "U3") (pin "13") (pinfunction "Q4_13") (pintype "output+no_connect"))
    )
    (net (code "37") (name "unconnected-(X1-Pad1)") (class "Default")
      (node (ref "X1") (pin "1") (pinfunction "1_1") (pintype "passive+no_connect"))
    )
    (net (code "38") (name "unconnected-(X1-Pad5)") (class "Default")
      (node (ref "X1") (pin "5") (pinfunction "5_5") (pintype "passive+no_connect"))
    )
  )
)
